# USBug.net
KiCad netlist of a schematic drawn in EAGLE
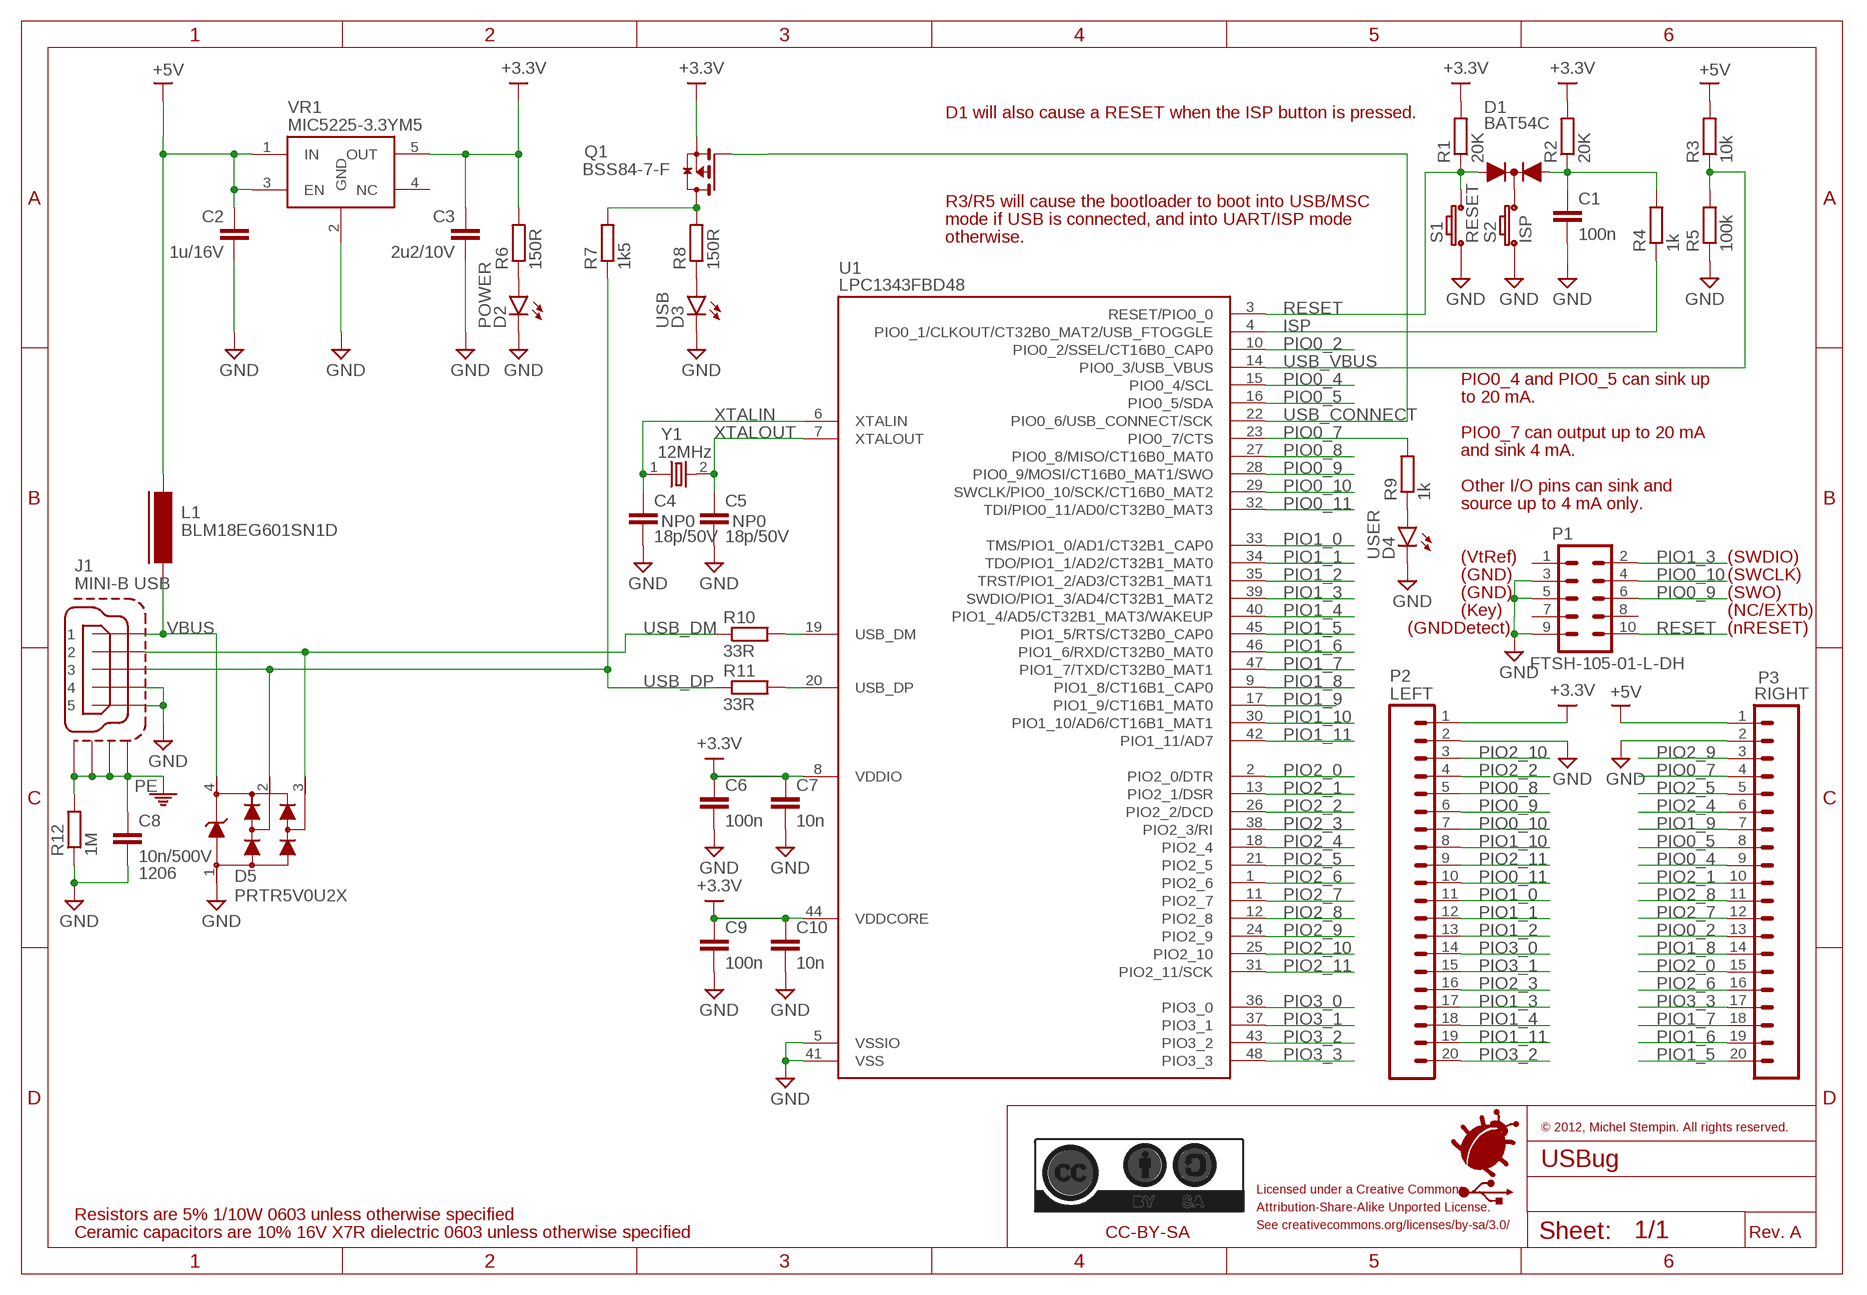
[diagram p0: schematic, sheet 1]

(export (version "E")
  (design (tool "Eeschema 10.0.6"))
  (components
    (comp (ref "C1")
      (value "100n")
      (footprint "eagle-import:CAP_0603")
      (libsource (lib "eagle-import") (part "CAP_0603"))
    )
    (comp (ref "C2")
      (value "1u/16V")
      (footprint "eagle-import:CAP_0603")
      (libsource (lib "eagle-import") (part "CAP_0603"))
    )
    (comp (ref "C3")
      (value "2u2/10V")
      (footprint "eagle-import:CAP_0603")
      (libsource (lib "eagle-import") (part "CAP_0603"))
    )
    (comp (ref "C4")
      (value "18p/50V")
      (footprint "eagle-import:CAP_0603")
      (fields (field (name "DIELECTRIC") "NP0"))
      (libsource (lib "eagle-import") (part "CAP_0603"))
    )
    (comp (ref "C5")
      (value "18p/50V")
      (footprint "eagle-import:CAP_0603")
      (fields (field (name "DIELECTRIC") "NP0"))
      (libsource (lib "eagle-import") (part "CAP_0603"))
    )
    (comp (ref "C6")
      (value "100n")
      (footprint "eagle-import:CAP_0603")
      (libsource (lib "eagle-import") (part "CAP_0603"))
    )
    (comp (ref "C7")
      (value "10n")
      (footprint "eagle-import:CAP_0603")
      (libsource (lib "eagle-import") (part "CAP_0603"))
    )
    (comp (ref "C8") (value "10n/500V") (footprint "1206") (libsource (lib "eagle-import") (part "CAP_1206")))
    (comp (ref "C9")
      (value "100n")
      (footprint "eagle-import:CAP_0603")
      (libsource (lib "eagle-import") (part "CAP_0603"))
    )
    (comp (ref "C10")
      (value "10n")
      (footprint "eagle-import:CAP_0603")
      (libsource (lib "eagle-import") (part "CAP_0603"))
    )
    (comp (ref "D1")
      (value "BAT54C")
      (footprint "eagle-import:SOT23-R")
      (libsource (lib "eagle-import") (part "BAT54C"))
    )
    (comp (ref "D2")
      (value "POWER")
      (footprint "eagle-import:LED_0805")
      (libsource (lib "eagle-import") (part "LED_0805"))
    )
    (comp (ref "D3")
      (value "USB")
      (footprint "eagle-import:LED_0805")
      (libsource (lib "eagle-import") (part "LED_0805"))
    )
    (comp (ref "D4")
      (value "USER")
      (footprint "eagle-import:LED_0805")
      (libsource (lib "eagle-import") (part "LED_0805"))
    )
    (comp (ref "D5")
      (value "PRTR5V0U2X")
      (footprint "eagle-import:SOT143B")
      (libsource (lib "eagle-import") (part "PRTR5V0U2X"))
    )
    (comp (ref "J1")
      (value "MINI-B USB")
      (footprint "eagle-import:UX60-MB-5ST")
      (libsource (lib "eagle-import") (part "MINI-B_USBUX60-MB-5ST"))
    )
    (comp (ref "L1")
      (value "BLM18EG601SN1D")
      (footprint "eagle-import:FB_0603")
      (libsource (lib "eagle-import") (part "FERRITE_BEAD0603"))
    )
    (comp (ref "LOGO")
      (value "USBUG")
      (footprint "eagle-import:USBUG")
      (libsource (lib "eagle-import") (part "USBUG"))
    )
    (comp (ref "P1")
      (value "FTSH-105-01-L-DH")
      (footprint "eagle-import:FTSH-105-01-L-DH")
      (libsource (lib "eagle-import") (part "FTSH-105-01-L-DH"))
    )
    (comp (ref "P2")
      (value "LEFT")
      (footprint "eagle-import:SPARKFUN_1X20_LOCK")
      (libsource (lib "eagle-import") (part "HEADER_1X20_LOCK"))
    )
    (comp (ref "P3")
      (value "RIGHT")
      (footprint "eagle-import:SPARKFUN_1X20_LOCK")
      (libsource (lib "eagle-import") (part "HEADER_1X20_LOCK"))
    )
    (comp (ref "Q1")
      (value "BSS84-7-F")
      (footprint "eagle-import:SOT23-R")
      (libsource (lib "eagle-import") (part "BSS84-7-F"))
    )
    (comp (ref "R1")
      (value "20K")
      (footprint "eagle-import:RES_0603")
      (libsource (lib "eagle-import") (part "RES_0603"))
    )
    (comp (ref "R2")
      (value "20K")
      (footprint "eagle-import:RES_0603")
      (libsource (lib "eagle-import") (part "RES_0603"))
    )
    (comp (ref "R3")
      (value "10k")
      (footprint "eagle-import:RES_0603")
      (libsource (lib "eagle-import") (part "RES_0603"))
    )
    (comp (ref "R4")
      (value "1k")
      (footprint "eagle-import:RES_0603")
      (libsource (lib "eagle-import") (part "RES_0603"))
    )
    (comp (ref "R5")
      (value "100k")
      (footprint "eagle-import:RES_0603")
      (libsource (lib "eagle-import") (part "RES_0603"))
    )
    (comp (ref "R6")
      (value "150R")
      (footprint "eagle-import:RES_0603")
      (libsource (lib "eagle-import") (part "RES_0603"))
    )
    (comp (ref "R7")
      (value "1k5")
      (footprint "eagle-import:RES_0603")
      (libsource (lib "eagle-import") (part "RES_0603"))
    )
    (comp (ref "R8")
      (value "150R")
      (footprint "eagle-import:RES_0603")
      (libsource (lib "eagle-import") (part "RES_0603"))
    )
    (comp (ref "R9")
      (value "1k")
      (footprint "eagle-import:RES_0603")
      (libsource (lib "eagle-import") (part "RES_0603"))
    )
    (comp (ref "R10")
      (value "33R")
      (footprint "eagle-import:RES_0603")
      (libsource (lib "eagle-import") (part "RES_0603"))
    )
    (comp (ref "R11")
      (value "33R")
      (footprint "eagle-import:RES_0603")
      (libsource (lib "eagle-import") (part "RES_0603"))
    )
    (comp (ref "R12")
      (value "1M")
      (footprint "eagle-import:RES_0603")
      (libsource (lib "eagle-import") (part "RES_0603"))
    )
    (comp (ref "S1")
      (value "RESET")
      (footprint "eagle-import:ADTSM3")
      (libsource (lib "eagle-import") (part "SPST_SWITCH"))
    )
    (comp (ref "S2")
      (value "ISP")
      (footprint "eagle-import:ADTSM3")
      (libsource (lib "eagle-import") (part "SPST_SWITCH"))
    )
    (comp (ref "U1")
      (value "LPC1343FBD48")
      (footprint "eagle-import:LQFP48")
      (libsource (lib "eagle-import") (part "LPC1343FBD48"))
    )
    (comp (ref "VR1")
      (value "MIC5225-3.3YM5")
      (footprint "eagle-import:SOT23-5")
      (fields (field (name "VOLTAGE") "3.3V"))
      (libsource (lib "eagle-import") (part "MIC5225YM5-3.3"))
    )
    (comp (ref "Y1")
      (value "12MHz")
      (footprint "eagle-import:NX5032GA")
      (libsource (lib "eagle-import") (part "CRYSTAL_50X32"))
    )
  )
  (nets
    (net (code "1") (name "+3.3V") (class "Default")
      (node (ref "C10") (pin "1") (pinfunction "1_1") (pintype "passive"))
      (node (ref "C3") (pin "1") (pinfunction "1_1") (pintype "passive"))
      (node (ref "C6") (pin "1") (pinfunction "1_1") (pintype "passive"))
      (node (ref "C7") (pin "1") (pinfunction "1_1") (pintype "passive"))
      (node (ref "C9") (pin "1") (pinfunction "1_1") (pintype "passive"))
      (node (ref "P2") (pin "1") (pinfunction "1_1") (pintype "passive"))
      (node (ref "Q1") (pin "2") (pinfunction "S_2") (pintype "passive"))
      (node (ref "R1") (pin "2") (pinfunction "2_2") (pintype "passive"))
      (node (ref "R2") (pin "2") (pinfunction "2_2") (pintype "passive"))
      (node (ref "R6") (pin "2") (pinfunction "2_2") (pintype "passive"))
      (node (ref "U1") (pin "44") (pinfunction "VDDCORE_44") (pintype "passive"))
      (node (ref "U1") (pin "8") (pinfunction "VDDIO_8") (pintype "passive"))
      (node (ref "VR1") (pin "5") (pinfunction "OUT_5") (pintype "passive"))
    )
    (net (code "2") (name "+5V") (class "Default")
      (node (ref "C2") (pin "1") (pinfunction "1_1") (pintype "passive"))
      (node (ref "L1") (pin "1") (pinfunction "1_1") (pintype "passive"))
      (node (ref "P3") (pin "1") (pinfunction "1_1") (pintype "passive"))
      (node (ref "R3") (pin "2") (pinfunction "2_2") (pintype "passive"))
      (node (ref "VR1") (pin "1") (pinfunction "IN_1") (pintype "passive"))
      (node (ref "VR1") (pin "3") (pinfunction "EN_3") (pintype "input"))
    )
    (net (code "3") (name "/ISP") (class "Default")
      (node (ref "R4") (pin "1") (pinfunction "1_1") (pintype "passive"))
      (node (ref "U1") (pin "4") (pinfunction "PIO0_1/CLKOUT/CT32B0_MAT2/USB_FTOGGLE_4") (pintype "bidirectional"))
    )
    (net (code "4") (name "/PIO0_2") (class "Default")
      (node (ref "P3") (pin "13") (pinfunction "13_13") (pintype "passive"))
      (node (ref "U1") (pin "10") (pinfunction "PIO0_2/SSEL/CT16B0_CAP0_10") (pintype "bidirectional"))
    )
    (net (code "5") (name "/PIO0_4") (class "Default")
      (node (ref "P3") (pin "9") (pinfunction "9_9") (pintype "passive"))
      (node (ref "U1") (pin "15") (pinfunction "PIO0_4/SCL_15") (pintype "bidirectional"))
    )
    (net (code "6") (name "/PIO0_5") (class "Default")
      (node (ref "P3") (pin "8") (pinfunction "8_8") (pintype "passive"))
      (node (ref "U1") (pin "16") (pinfunction "PIO0_5/SDA_16") (pintype "bidirectional"))
    )
    (net (code "7") (name "/PIO0_7") (class "Default")
      (node (ref "P3") (pin "4") (pinfunction "4_4") (pintype "passive"))
      (node (ref "R9") (pin "2") (pinfunction "2_2") (pintype "passive"))
      (node (ref "U1") (pin "23") (pinfunction "PIO0_7/CTS_23") (pintype "bidirectional"))
    )
    (net (code "8") (name "/PIO0_8") (class "Default")
      (node (ref "P2") (pin "5") (pinfunction "5_5") (pintype "passive"))
      (node (ref "U1") (pin "27") (pinfunction "PIO0_8/MISO/CT16B0_MAT0_27") (pintype "bidirectional"))
    )
    (net (code "9") (name "/PIO0_9") (class "Default")
      (node (ref "P1") (pin "6") (pinfunction "6_6") (pintype "passive"))
      (node (ref "P2") (pin "6") (pinfunction "6_6") (pintype "passive"))
      (node (ref "U1") (pin "28") (pinfunction "PIO0_9/MOSI/CT16B0_MAT1/SWO_28") (pintype "bidirectional"))
    )
    (net (code "10") (name "/PIO0_10") (class "Default")
      (node (ref "P1") (pin "4") (pinfunction "4_4") (pintype "passive"))
      (node (ref "P2") (pin "7") (pinfunction "7_7") (pintype "passive"))
      (node (ref "U1") (pin "29") (pinfunction "SWCLK/PIO0_10/SCK/CT16B0_MAT2_29") (pintype "bidirectional"))
    )
    (net (code "11") (name "/PIO0_11") (class "Default")
      (node (ref "P2") (pin "10") (pinfunction "10_10") (pintype "passive"))
      (node (ref "U1") (pin "32") (pinfunction "TDI/PIO0_11/AD0/CT32B0_MAT3_32") (pintype "bidirectional"))
    )
    (net (code "12") (name "/PIO1_0") (class "Default")
      (node (ref "P2") (pin "11") (pinfunction "11_11") (pintype "passive"))
      (node (ref "U1") (pin "33") (pinfunction "TMS/PIO1_0/AD1/CT32B1_CAP0_33") (pintype "bidirectional"))
    )
    (net (code "13") (name "/PIO1_1") (class "Default")
      (node (ref "P2") (pin "12") (pinfunction "12_12") (pintype "passive"))
      (node (ref "U1") (pin "34") (pinfunction "TDO/PIO1_1/AD2/CT32B1_MAT0_34") (pintype "bidirectional"))
    )
    (net (code "14") (name "/PIO1_2") (class "Default")
      (node (ref "P2") (pin "13") (pinfunction "13_13") (pintype "passive"))
      (node (ref "U1") (pin "35") (pinfunction "TRST/PIO1_2/AD3/CT32B1_MAT1_35") (pintype "bidirectional"))
    )
    (net (code "15") (name "/PIO1_3") (class "Default")
      (node (ref "P1") (pin "2") (pinfunction "2_2") (pintype "passive"))
      (node (ref "P2") (pin "17") (pinfunction "17_17") (pintype "passive"))
      (node (ref "U1") (pin "39") (pinfunction "SWDIO/PIO1_3/AD4/CT32B1_MAT2_39") (pintype "bidirectional"))
    )
    (net (code "16") (name "/PIO1_4") (class "Default")
      (node (ref "P2") (pin "18") (pinfunction "18_18") (pintype "passive"))
      (node (ref "U1") (pin "40") (pinfunction "PIO1_4/AD5/CT32B1_MAT3/WAKEUP_40") (pintype "bidirectional"))
    )
    (net (code "17") (name "/PIO1_5") (class "Default")
      (node (ref "P3") (pin "20") (pinfunction "20_20") (pintype "passive"))
      (node (ref "U1") (pin "45") (pinfunction "PIO1_5/RTS/CT32B0_CAP0_45") (pintype "bidirectional"))
    )
    (net (code "18") (name "/PIO1_6") (class "Default")
      (node (ref "P3") (pin "19") (pinfunction "19_19") (pintype "passive"))
      (node (ref "U1") (pin "46") (pinfunction "PIO1_6/RXD/CT32B0_MAT0_46") (pintype "bidirectional"))
    )
    (net (code "19") (name "/PIO1_7") (class "Default")
      (node (ref "P3") (pin "18") (pinfunction "18_18") (pintype "passive"))
      (node (ref "U1") (pin "47") (pinfunction "PIO1_7/TXD/CT32B0_MAT1_47") (pintype "bidirectional"))
    )
    (net (code "20") (name "/PIO1_8") (class "Default")
      (node (ref "P3") (pin "14") (pinfunction "14_14") (pintype "passive"))
      (node (ref "U1") (pin "9") (pinfunction "PIO1_8/CT16B1_CAP0_9") (pintype "bidirectional"))
    )
    (net (code "21") (name "/PIO1_9") (class "Default")
      (node (ref "P3") (pin "7") (pinfunction "7_7") (pintype "passive"))
      (node (ref "U1") (pin "17") (pinfunction "PIO1_9/CT16B1_MAT0_17") (pintype "bidirectional"))
    )
    (net (code "22") (name "/PIO1_10") (class "Default")
      (node (ref "P2") (pin "8") (pinfunction "8_8") (pintype "passive"))
      (node (ref "U1") (pin "30") (pinfunction "PIO1_10/AD6/CT16B1_MAT1_30") (pintype "bidirectional"))
    )
    (net (code "23") (name "/PIO1_11") (class "Default")
      (node (ref "P2") (pin "19") (pinfunction "19_19") (pintype "passive"))
      (node (ref "U1") (pin "42") (pinfunction "PIO1_11/AD7_42") (pintype "bidirectional"))
    )
    (net (code "24") (name "/PIO2_0") (class "Default")
      (node (ref "P3") (pin "15") (pinfunction "15_15") (pintype "passive"))
      (node (ref "U1") (pin "2") (pinfunction "PIO2_0/DTR_2") (pintype "bidirectional"))
    )
    (net (code "25") (name "/PIO2_1") (class "Default")
      (node (ref "P3") (pin "10") (pinfunction "10_10") (pintype "passive"))
      (node (ref "U1") (pin "13") (pinfunction "PIO2_1/DSR_13") (pintype "bidirectional"))
    )
    (net (code "26") (name "/PIO2_2") (class "Default")
      (node (ref "P2") (pin "4") (pinfunction "4_4") (pintype "passive"))
      (node (ref "U1") (pin "26") (pinfunction "PIO2_2/DCD_26") (pintype "bidirectional"))
    )
    (net (code "27") (name "/PIO2_3") (class "Default")
      (node (ref "P2") (pin "16") (pinfunction "16_16") (pintype "passive"))
      (node (ref "U1") (pin "38") (pinfunction "PIO2_3/RI_38") (pintype "bidirectional"))
    )
    (net (code "28") (name "/PIO2_4") (class "Default")
      (node (ref "P3") (pin "6") (pinfunction "6_6") (pintype "passive"))
      (node (ref "U1") (pin "18") (pinfunction "PIO2_4_18") (pintype "bidirectional"))
    )
    (net (code "29") (name "/PIO2_5") (class "Default")
      (node (ref "P3") (pin "5") (pinfunction "5_5") (pintype "passive"))
      (node (ref "U1") (pin "21") (pinfunction "PIO2_5_21") (pintype "bidirectional"))
    )
    (net (code "30") (name "/PIO2_6") (class "Default")
      (node (ref "P3") (pin "16") (pinfunction "16_16") (pintype "passive"))
      (node (ref "U1") (pin "1") (pinfunction "PIO2_6_1") (pintype "bidirectional"))
    )
    (net (code "31") (name "/PIO2_7") (class "Default")
      (node (ref "P3") (pin "12") (pinfunction "12_12") (pintype "passive"))
      (node (ref "U1") (pin "11") (pinfunction "PIO2_7_11") (pintype "bidirectional"))
    )
    (net (code "32") (name "/PIO2_8") (class "Default")
      (node (ref "P3") (pin "11") (pinfunction "11_11") (pintype "passive"))
      (node (ref "U1") (pin "12") (pinfunction "PIO2_8_12") (pintype "bidirectional"))
    )
    (net (code "33") (name "/PIO2_9") (class "Default")
      (node (ref "P3") (pin "3") (pinfunction "3_3") (pintype "passive"))
      (node (ref "U1") (pin "24") (pinfunction "PIO2_9_24") (pintype "bidirectional"))
    )
    (net (code "34") (name "/PIO2_10") (class "Default")
      (node (ref "P2") (pin "3") (pinfunction "3_3") (pintype "passive"))
      (node (ref "U1") (pin "25") (pinfunction "PIO2_10_25") (pintype "bidirectional"))
    )
    (net (code "35") (name "/PIO2_11") (class "Default")
      (node (ref "P2") (pin "9") (pinfunction "9_9") (pintype "passive"))
      (node (ref "U1") (pin "31") (pinfunction "PIO2_11/SCK_31") (pintype "bidirectional"))
    )
    (net (code "36") (name "/PIO3_0") (class "Default")
      (node (ref "P2") (pin "14") (pinfunction "14_14") (pintype "passive"))
      (node (ref "U1") (pin "36") (pinfunction "PIO3_0_36") (pintype "bidirectional"))
    )
    (net (code "37") (name "/PIO3_1") (class "Default")
      (node (ref "P2") (pin "15") (pinfunction "15_15") (pintype "passive"))
      (node (ref "U1") (pin "37") (pinfunction "PIO3_1_37") (pintype "bidirectional"))
    )
    (net (code "38") (name "/PIO3_2") (class "Default")
      (node (ref "P2") (pin "20") (pinfunction "20_20") (pintype "passive"))
      (node (ref "U1") (pin "43") (pinfunction "PIO3_2_43") (pintype "bidirectional"))
    )
    (net (code "39") (name "/PIO3_3") (class "Default")
      (node (ref "P3") (pin "17") (pinfunction "17_17") (pintype "passive"))
      (node (ref "U1") (pin "48") (pinfunction "PIO3_3_48") (pintype "bidirectional"))
    )
    (net (code "40") (name "/RESET") (class "Default")
      (node (ref "D1") (pin "1") (pinfunction "A1_1") (pintype "passive"))
      (node (ref "P1") (pin "10") (pinfunction "10_10") (pintype "passive"))
      (node (ref "R1") (pin "1") (pinfunction "1_1") (pintype "passive"))
      (node (ref "S1") (pin "1") (pinfunction "1_1") (pintype "bidirectional"))
      (node (ref "U1") (pin "3") (pinfunction "RESET/PIO0_0_3") (pintype "bidirectional"))
    )
    (net (code "41") (name "/USB_CONNECT") (class "Default")
      (node (ref "Q1") (pin "1") (pinfunction "G_1") (pintype "passive"))
      (node (ref "U1") (pin "22") (pinfunction "PIO0_6/USB_CONNECT/SCK_22") (pintype "bidirectional"))
    )
    (net (code "42") (name "/USB_DM") (class "Default")
      (node (ref "D5") (pin "3") (pinfunction "P$3_3") (pintype "passive"))
      (node (ref "J1") (pin "2") (pinfunction "2_2") (pintype "passive"))
      (node (ref "R10") (pin "1") (pinfunction "1_1") (pintype "passive"))
    )
    (net (code "43") (name "/USB_DP") (class "Default")
      (node (ref "D5") (pin "2") (pinfunction "P$2_2") (pintype "passive"))
      (node (ref "J1") (pin "3") (pinfunction "3_3") (pintype "passive"))
      (node (ref "R11") (pin "1") (pinfunction "1_1") (pintype "passive"))
      (node (ref "R7") (pin "1") (pinfunction "1_1") (pintype "passive"))
    )
    (net (code "44") (name "/USB_VBUS") (class "Default")
      (node (ref "R3") (pin "1") (pinfunction "1_1") (pintype "passive"))
      (node (ref "R5") (pin "2") (pinfunction "2_2") (pintype "passive"))
      (node (ref "U1") (pin "14") (pinfunction "PIO0_3/USB_VBUS_14") (pintype "bidirectional"))
    )
    (net (code "45") (name "/VBUS") (class "Default")
      (node (ref "D5") (pin "4") (pinfunction "P$4_4") (pintype "passive"))
      (node (ref "J1") (pin "1") (pinfunction "1_1") (pintype "passive"))
      (node (ref "L1") (pin "2") (pinfunction "2_2") (pintype "passive"))
    )
    (net (code "46") (name "/XTALIN") (class "Default")
      (node (ref "C4") (pin "1") (pinfunction "1_1") (pintype "passive"))
      (node (ref "U1") (pin "6") (pinfunction "XTALIN_6") (pintype "passive"))
      (node (ref "Y1") (pin "1") (pinfunction "1_1") (pintype "passive"))
    )
    (net (code "47") (name "/XTALOUT") (class "Default")
      (node (ref "C5") (pin "1") (pinfunction "1_1") (pintype "passive"))
      (node (ref "U1") (pin "7") (pinfunction "XTALOUT_7") (pintype "passive"))
      (node (ref "Y1") (pin "2") (pinfunction "2_2") (pintype "passive"))
    )
    (net (code "48") (name "GND") (class "Default")
      (node (ref "C1") (pin "2") (pinfunction "2_2") (pintype "passive"))
      (node (ref "C10") (pin "2") (pinfunction "2_2") (pintype "passive"))
      (node (ref "C2") (pin "2") (pinfunction "2_2") (pintype "passive"))
      (node (ref "C3") (pin "2") (pinfunction "2_2") (pintype "passive"))
      (node (ref "C4") (pin "2") (pinfunction "2_2") (pintype "passive"))
      (node (ref "C5") (pin "2") (pinfunction "2_2") (pintype "passive"))
      (node (ref "C6") (pin "2") (pinfunction "2_2") (pintype "passive"))
      (node (ref "C7") (pin "2") (pinfunction "2_2") (pintype "passive"))
      (node (ref "C8") (pin "2") (pinfunction "2_2") (pintype "passive"))
      (node (ref "C9") (pin "2") (pinfunction "2_2") (pintype "passive"))
      (node (ref "D2") (pin "C") (pinfunction "C_C") (pintype "passive"))
      (node (ref "D3") (pin "C") (pinfunction "C_C") (pintype "passive"))
      (node (ref "D4") (pin "C") (pinfunction "C_C") (pintype "passive"))
      (node (ref "D5") (pin "1") (pinfunction "P$1_1") (pintype "passive"))
      (node (ref "J1") (pin "4") (pinfunction "4_4") (pintype "passive"))
      (node (ref "J1") (pin "5") (pinfunction "5_5") (pintype "passive"))
      (node (ref "P1") (pin "3") (pinfunction "3_3") (pintype "passive"))
      (node (ref "P1") (pin "5") (pinfunction "5_5") (pintype "passive"))
      (node (ref "P1") (pin "9") (pinfunction "9_9") (pintype "passive"))
      (node (ref "P2") (pin "2") (pinfunction "2_2") (pintype "passive"))
      (node (ref "P3") (pin "2") (pinfunction "2_2") (pintype "passive"))
      (node (ref "R12") (pin "1") (pinfunction "1_1") (pintype "passive"))
      (node (ref "R5") (pin "1") (pinfunction "1_1") (pintype "passive"))
      (node (ref "S1") (pin "2") (pinfunction "P$2_2") (pintype "bidirectional"))
      (node (ref "S2") (pin "2") (pinfunction "P$2_2") (pintype "bidirectional"))
      (node (ref "U1") (pin "41") (pinfunction "VSS_41") (pintype "passive"))
      (node (ref "U1") (pin "5") (pinfunction "VSSIO_5") (pintype "passive"))
      (node (ref "VR1") (pin "2") (pinfunction "GND_2") (pintype "passive"))
    )
    (net (code "49") (name "Net-(D1-A2)") (class "Default")
      (node (ref "C1") (pin "1") (pinfunction "1_1") (pintype "passive"))
      (node (ref "D1") (pin "2") (pinfunction "A2_2") (pintype "passive"))
      (node (ref "R2") (pin "1") (pinfunction "1_1") (pintype "passive"))
      (node (ref "R4") (pin "2") (pinfunction "2_2") (pintype "passive"))
    )
    (net (code "50") (name "Net-(D1-C)") (class "Default")
      (node (ref "D1") (pin "3") (pinfunction "C_3") (pintype "passive"))
      (node (ref "S2") (pin "1") (pinfunction "1_1") (pintype "bidirectional"))
    )
    (net (code "51") (name "Net-(D2-PadA)") (class "Default")
      (node (ref "D2") (pin "A") (pinfunction "A_A") (pintype "passive"))
      (node (ref "R6") (pin "1") (pinfunction "1_1") (pintype "passive"))
    )
    (net (code "52") (name "Net-(D3-PadA)") (class "Default")
      (node (ref "D3") (pin "A") (pinfunction "A_A") (pintype "passive"))
      (node (ref "R8") (pin "1") (pinfunction "1_1") (pintype "passive"))
    )
    (net (code "53") (name "Net-(D4-PadA)") (class "Default")
      (node (ref "D4") (pin "A") (pinfunction "A_A") (pintype "passive"))
      (node (ref "R9") (pin "1") (pinfunction "1_1") (pintype "passive"))
    )
    (net (code "54") (name "Net-(Q1-D)") (class "Default")
      (node (ref "Q1") (pin "3") (pinfunction "D_3") (pintype "passive"))
      (node (ref "R7") (pin "2") (pinfunction "2_2") (pintype "passive"))
      (node (ref "R8") (pin "2") (pinfunction "2_2") (pintype "passive"))
    )
    (net (code "55") (name "Net-(U1-USB_DM)") (class "Default")
      (node (ref "R10") (pin "2") (pinfunction "2_2") (pintype "passive"))
      (node (ref "U1") (pin "19") (pinfunction "USB_DM_19") (pintype "passive"))
    )
    (net (code "56") (name "Net-(U1-USB_DP)") (class "Default")
      (node (ref "R11") (pin "2") (pinfunction "2_2") (pintype "passive"))
      (node (ref "U1") (pin "20") (pinfunction "USB_DP_20") (pintype "bidirectional"))
    )
    (net (code "57") (name "PE") (class "Default")
      (node (ref "C8") (pin "1") (pinfunction "1_1") (pintype "passive"))
      (node (ref "J1") (pin "M1") (pinfunction "M1_M1") (pintype "passive"))
      (node (ref "J1") (pin "M2") (pinfunction "M2_M2") (pintype "passive"))
      (node (ref "J1") (pin "M3") (pinfunction "M3_M3") (pintype "passive"))
      (node (ref "J1") (pin "M4") (pinfunction "M4_M4") (pintype "passive"))
      (node (ref "R12") (pin "2") (pinfunction "2_2") (pintype "passive"))
    )
    (net (code "58") (name "unconnected-(P1-Pad1)") (class "Default")
      (node (ref "P1") (pin "1") (pinfunction "1_1") (pintype "passive"))
    )
    (net (code "59") (name "unconnected-(P1-Pad7)") (class "Default")
      (node (ref "P1") (pin "7") (pinfunction "7_7") (pintype "passive"))
    )
    (net (code "60") (name "unconnected-(P1-Pad8)") (class "Default")
      (node (ref "P1") (pin "8") (pinfunction "8_8") (pintype "passive"))
    )
    (net (code "61") (name "unconnected-(VR1-NC-Pad4)") (class "Default")
      (node (ref "VR1") (pin "4") (pinfunction "NC_4") (pintype "no_connect"))
    )
  )
)
